# Bopit.net
KiCad netlist of a schematic drawn in Altium Designer
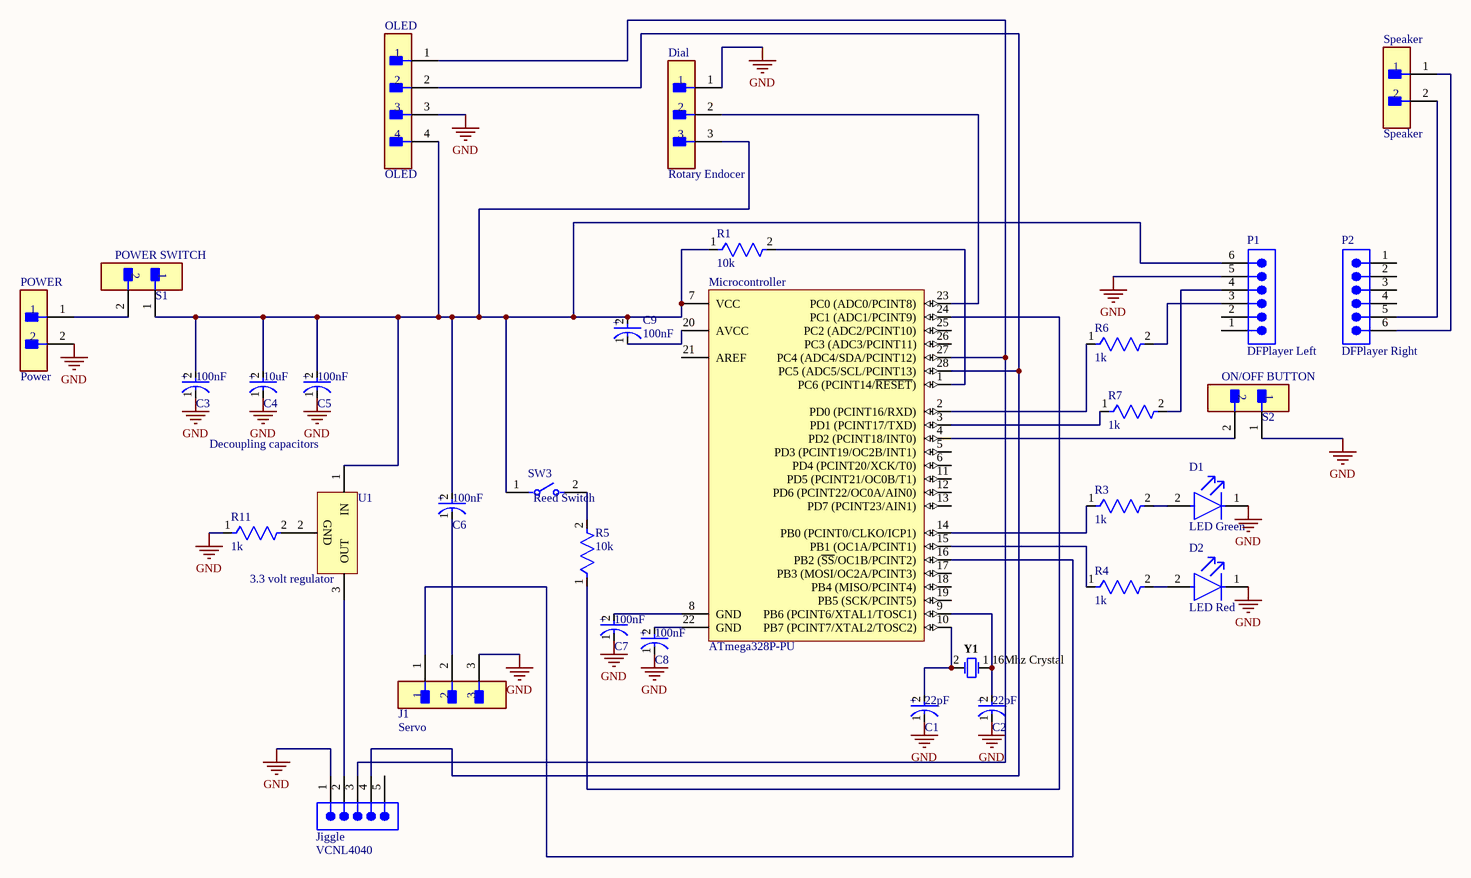
[diagram p0: Bopit.SchDoc]

(export (version "E")
  (design (tool "Eeschema 10.0.6"))
  (components
    (comp (ref "C1")
      (value "22pF")
      (footprint "FP-RAD-TH-D_6_3_0_5-L_11-MFG")
      (description "Aluminum Electrolytic Capacitors (Radial Lead Type) 2.2uF ±20% 250V")
      (fields (field (name "TOLERANCE") "20%"))
      (libsource (lib "Altium Content Vault") (part "203bc49f2ac43e59fd269a8c329ed05"))
    )
    (comp (ref "C2")
      (value "22pF")
      (footprint "FP-RAD-TH-D_6_3_0_5-L_11-MFG")
      (description "Aluminum Electrolytic Capacitors (Radial Lead Type) 2.2uF ±20% 250V")
      (fields (field (name "TOLERANCE") "20%"))
      (libsource (lib "Altium Content Vault") (part "203bc49f2ac43e59fd269a8c329ed05"))
    )
    (comp (ref "C3")
      (value "100nF")
      (footprint "FP-RAD-TH-D_6_3_0_5-L_11-MFG")
      (description "Aluminum Electrolytic Capacitors (Radial Lead Type) 2.2uF ±20% 250V")
      (fields (field (name "TOLERANCE") "20%"))
      (libsource (lib "Altium Content Vault") (part "203bc49f2ac43e59fd269a8c329ed05"))
    )
    (comp (ref "C4")
      (value "10uF")
      (footprint "FP-RAD-TH-D_6_3_0_5-L_11-MFG")
      (description "Aluminum Electrolytic Capacitors (Radial Lead Type) 2.2uF ±20% 250V")
      (fields (field (name "TOLERANCE") "20%"))
      (libsource (lib "Altium Content Vault") (part "203bc49f2ac43e59fd269a8c329ed05"))
    )
    (comp (ref "C5")
      (value "100nF")
      (footprint "FP-RAD-TH-D_6_3_0_5-L_11-MFG")
      (description "Aluminum Electrolytic Capacitors (Radial Lead Type) 2.2uF ±20% 250V")
      (fields (field (name "TOLERANCE") "20%"))
      (libsource (lib "Altium Content Vault") (part "203bc49f2ac43e59fd269a8c329ed05"))
    )
    (comp (ref "C6")
      (value "100nF")
      (footprint "FP-RAD-TH-D_6_3_0_5-L_11-MFG")
      (description "Aluminum Electrolytic Capacitors (Radial Lead Type) 2.2uF ±20% 250V")
      (fields (field (name "TOLERANCE") "20%"))
      (libsource (lib "Altium Content Vault") (part "203bc49f2ac43e59fd269a8c329ed05"))
    )
    (comp (ref "C7")
      (value "100nF")
      (footprint "FP-RAD-TH-D_6_3_0_5-L_11-MFG")
      (description "Aluminum Electrolytic Capacitors (Radial Lead Type) 2.2uF ±20% 250V")
      (fields (field (name "TOLERANCE") "20%"))
      (libsource (lib "Altium Content Vault") (part "203bc49f2ac43e59fd269a8c329ed05"))
    )
    (comp (ref "C8")
      (value "100nF")
      (footprint "FP-RAD-TH-D_6_3_0_5-L_11-MFG")
      (description "Aluminum Electrolytic Capacitors (Radial Lead Type) 2.2uF ±20% 250V")
      (fields (field (name "TOLERANCE") "20%"))
      (libsource (lib "Altium Content Vault") (part "203bc49f2ac43e59fd269a8c329ed05"))
    )
    (comp (ref "C9")
      (value "100nF")
      (footprint "FP-RAD-TH-D_6_3_0_5-L_11-MFG")
      (description "Aluminum Electrolytic Capacitors (Radial Lead Type) 2.2uF ±20% 250V")
      (fields (field (name "TOLERANCE") "20%"))
      (libsource (lib "Altium Content Vault") (part "203bc49f2ac43e59fd269a8c329ed05"))
    )
    (comp (ref "D1")
      (value "LED Green")
      (footprint "FP-SSL-LX5093YD-MFG")
      (description "LED YELLOW DIFFUSED T-1 3/4 T/H")
      (libsource (lib "Altium Content Vault") (part "8706943c75ba83719d021d2fdc84c58"))
    )
    (comp (ref "D2")
      (value "LED Red")
      (footprint "FP-SSL-LX5093YD-MFG")
      (description "LED YELLOW DIFFUSED T-1 3/4 T/H")
      (libsource (lib "Altium Content Vault") (part "8706943c75ba83719d021d2fdc84c58"))
    )
    (comp (ref "Dial")
      (value "Rotary Endocer")
      (footprint "FP-TSW-103-14-G-S-MFG")
      (description "CONN HEADER VERT 3POS 2.54MM")
      (libsource (lib "Altium Content Vault") (part "cd3439d6ef35ae5d9b27ec4fdd3e828"))
    )
    (comp (ref "J1")
      (value "Servo")
      (footprint "FP-TSW-103-14-G-S-MFG")
      (description "CONN HEADER VERT 3POS 2.54MM")
      (libsource (lib "") (part "cd3439d6ef35ae5d9b27ec4fdd3e828_1"))
    )
    (comp (ref "Jiggle")
      (value "VCNL4040")
      (footprint "SMTC-TSW-105-05-X-S")
      (description "0.025\" SQ Post Header, Through-hole, Vertical, -55 to 125 degC, 2.54 mm Pitch, 5-Pin, Male, RoHS")
      (fields (field (name "PARTNUMBER") "TSW-105-05-L-S") (field (name "MANUFACTURER") "Samtec"))
      (libsource (lib "Altium Content Vault") (part "SMTC-TSW-105-05-X-S"))
    )
    (comp (ref "Microcontroller")
      (value "ATmega328P-PU")
      (footprint "28P3")
      (libsource (lib "Altium Content Vault") (part "MC-8B-ATM48-IL28"))
    )
    (comp (ref "OLED")
      (value "OLED")
      (footprint "FP-TSW-104-22-G-S-MFG")
      (description "CONN HEADER VERT 4POS 2.54MM")
      (libsource (lib "Altium Content Vault") (part "299a8cea1bdcbc3624fe62c390fa72c"))
    )
    (comp (ref "P1")
      (value "DFPlayer Left")
      (footprint "SMTC-TSW-106-17-X-S-LL")
      (description "0.025\" SQ Post Header, Through-hole, Vertical, -55 to 125 degC, 2.54 mm Pitch, 6-Pin, Male, RoHS")
      (fields (field (name "PARTNUMBER") "TSW-106-17-L-S-LL") (field (name "MANUFACTURER") "Samtec"))
      (libsource (lib "Altium Content Vault") (part "SMTC-TSW-106-X-X-S-X"))
    )
    (comp (ref "P2")
      (value "DFPlayer Right")
      (footprint "SMTC-TSW-106-17-X-S-LL")
      (description "0.025\" SQ Post Header, Through-hole, Vertical, -55 to 125 degC, 2.54 mm Pitch, 6-Pin, Male, RoHS")
      (fields (field (name "PARTNUMBER") "TSW-106-17-L-S-LL") (field (name "MANUFACTURER") "Samtec"))
      (libsource (lib "Altium Content Vault") (part "SMTC-TSW-106-X-X-S-X"))
    )
    (comp (ref "POWER")
      (value "Power")
      (footprint "FP-TMM-102-03-F-S-MFG")
      (description "CONN HEADER VERT 2POS 2MM")
      (libsource (lib "Altium Content Vault") (part "3bc925449376181038e59eaffc5286c"))
    )
    (comp (ref "R1")
      (value "10k")
      (footprint "FP-FMP100-MFG")
      (description "Resistor, 1 kOhm, ± 5%, 1 W, Axial Leaded, Metal Film, High Power Flame Proof")
      (fields (field (name "TOLERANCE") "5%"))
      (libsource (lib "Altium Content Vault") (part "FMP100JT-52-1K"))
    )
    (comp (ref "R3")
      (value "1k")
      (footprint "FP-FMP100-MFG")
      (description "Resistor, 1 kOhm, ± 5%, 1 W, Axial Leaded, Metal Film, High Power Flame Proof")
      (fields (field (name "TOLERANCE") "5%"))
      (libsource (lib "Altium Content Vault") (part "FMP100JT-52-1K"))
    )
    (comp (ref "R4")
      (value "1k")
      (footprint "FP-FMP100-MFG")
      (description "Resistor, 1 kOhm, ± 5%, 1 W, Axial Leaded, Metal Film, High Power Flame Proof")
      (fields (field (name "TOLERANCE") "5%"))
      (libsource (lib "Altium Content Vault") (part "FMP100JT-52-1K"))
    )
    (comp (ref "R5")
      (value "10k")
      (footprint "FP-FMP100-MFG")
      (description "Resistor, 1 kOhm, ± 5%, 1 W, Axial Leaded, Metal Film, High Power Flame Proof")
      (fields (field (name "TOLERANCE") "5%"))
      (libsource (lib "Altium Content Vault") (part "FMP100JT-52-1K"))
    )
    (comp (ref "R6")
      (value "1k")
      (footprint "FP-FMP100-MFG")
      (description "Resistor, 1 kOhm, ± 5%, 1 W, Axial Leaded, Metal Film, High Power Flame Proof")
      (fields (field (name "TOLERANCE") "5%"))
      (libsource (lib "Altium Content Vault") (part "FMP100JT-52-1K"))
    )
    (comp (ref "R7")
      (value "1k")
      (footprint "FP-FMP100-MFG")
      (description "Resistor, 1 kOhm, ± 5%, 1 W, Axial Leaded, Metal Film, High Power Flame Proof")
      (fields (field (name "TOLERANCE") "5%"))
      (libsource (lib "Altium Content Vault") (part "FMP100JT-52-1K"))
    )
    (comp (ref "R11")
      (value "1k")
      (footprint "FP-FMP100-MFG")
      (description "Resistor, 1 kOhm, ± 5%, 1 W, Axial Leaded, Metal Film, High Power Flame Proof")
      (fields (field (name "TOLERANCE") "5%"))
      (libsource (lib "Altium Content Vault") (part "FMP100JT-52-1K"))
    )
    (comp (ref "S1")
      (value "POWER SWITCH")
      (footprint "FP-TMM-102-04-G-S-MFG")
      (description "2MM TERMINAL STRIP")
      (libsource (lib "") (part "3bc925449376181038e59eaffc5286c_1"))
    )
    (comp (ref "S2")
      (value "ON/OFF BUTTON")
      (footprint "FP-TMM-102-04-G-S-MFG")
      (description "2MM TERMINAL STRIP")
      (libsource (lib "") (part "3bc925449376181038e59eaffc5286c_1"))
    )
    (comp (ref "Speaker")
      (value "Speaker")
      (footprint "FP-TMM-102-03-F-S-MFG")
      (description "CONN HEADER VERT 2POS 2MM")
      (libsource (lib "Altium Content Vault") (part "3bc925449376181038e59eaffc5286c"))
    )
    (comp (ref "SW3")
      (value "Reed Switch")
      (footprint "FP-MLRR-3-17-23-MFG")
      (description "SWITCH REED SPST-NO 700MA 140V")
      (libsource (lib "Altium Content Vault") (part "bb27bde45df87f1f469753f287ef5ae"))
    )
    (comp (ref "U1")
      (value "3.3 volt regulator")
      (footprint "ONSC-TO-220-3-221AB-01")
      (description "Positive Voltage Regulator, 1 A, 5 V, 0 to 125 degC, 3-Pin TO-220, RoHS, Tube")
      (fields (field (name "MANUFACTURER") "ON Semiconductor"))
      (libsource (lib "Altium Content Vault") (part "ONSC-MC7805CTG-TO-220-3"))
    )
    (comp (ref "Y1")
      (value "16Mhz Crystal")
      (footprint "FOX-FOXSLF160-20")
      (description "Resistance Weld Thru-Hole Crystal, 16 MHz, -20 to 70 degC, 2-Pin THD, RoHS, Bulk")
      (fields (field (name "TOLERANCE") "1%"))
      (libsource (lib "Altium Content Vault") (part "XTAL-1-2-2"))
    )
  )
  (nets
    (net (code "1") (name "GND") (class "Default")
      (node (ref "C1") (pin "1") (pinfunction "C_1") (pintype "passive"))
      (node (ref "C2") (pin "1") (pinfunction "C_1") (pintype "passive"))
      (node (ref "C3") (pin "1") (pinfunction "C_1") (pintype "passive"))
      (node (ref "C4") (pin "1") (pinfunction "C_1") (pintype "passive"))
      (node (ref "C5") (pin "1") (pinfunction "C_1") (pintype "passive"))
      (node (ref "C7") (pin "1") (pinfunction "C_1") (pintype "passive"))
      (node (ref "C8") (pin "1") (pinfunction "C_1") (pintype "passive"))
      (node (ref "D1") (pin "1") (pinfunction "C_1") (pintype "passive"))
      (node (ref "D2") (pin "1") (pinfunction "C_1") (pintype "passive"))
      (node (ref "Dial") (pin "1") (pinfunction "1_1") (pintype "passive"))
      (node (ref "J1") (pin "3") (pinfunction "3_3") (pintype "passive"))
      (node (ref "Jiggle") (pin "1") (pinfunction "1_1") (pintype "passive"))
      (node (ref "OLED") (pin "3") (pinfunction "3_3") (pintype "passive"))
      (node (ref "P1") (pin "5") (pinfunction "5_5") (pintype "passive"))
      (node (ref "POWER") (pin "2") (pinfunction "2_2") (pintype "passive"))
      (node (ref "R11") (pin "1") (pinfunction "1_1") (pintype "passive"))
      (node (ref "S2") (pin "1") (pinfunction "1_1") (pintype "passive"))
    )
    (net (code "2") (name "Net-(C1-A)") (class "Default")
      (node (ref "C1") (pin "2") (pinfunction "A_2") (pintype "passive"))
      (node (ref "Microcontroller") (pin "10") (pinfunction "PB7_(PCINT7/XTAL2/TOSC2)_10") (pintype "bidirectional"))
      (node (ref "Y1") (pin "2") (pinfunction "2_2") (pintype "passive"))
    )
    (net (code "3") (name "Net-(C2-A)") (class "Default")
      (node (ref "C2") (pin "2") (pinfunction "A_2") (pintype "passive"))
      (node (ref "Microcontroller") (pin "9") (pinfunction "PB6_(PCINT6/XTAL1/TOSC1)_9") (pintype "bidirectional"))
      (node (ref "Y1") (pin "1") (pinfunction "1_1") (pintype "passive"))
    )
    (net (code "4") (name "Net-(C3-A)") (class "Default")
      (node (ref "C3") (pin "2") (pinfunction "A_2") (pintype "passive"))
      (node (ref "C4") (pin "2") (pinfunction "A_2") (pintype "passive"))
      (node (ref "C5") (pin "2") (pinfunction "A_2") (pintype "passive"))
      (node (ref "C6") (pin "2") (pinfunction "A_2") (pintype "passive"))
      (node (ref "C9") (pin "2") (pinfunction "A_2") (pintype "passive"))
      (node (ref "Dial") (pin "3") (pinfunction "3_3") (pintype "passive"))
      (node (ref "Microcontroller") (pin "7") (pinfunction "VCC_7") (pintype "power_in"))
      (node (ref "OLED") (pin "4") (pinfunction "4_4") (pintype "passive"))
      (node (ref "P1") (pin "6") (pinfunction "6_6") (pintype "passive"))
      (node (ref "R1") (pin "1") (pinfunction "1_1") (pintype "passive"))
      (node (ref "S1") (pin "1") (pinfunction "1_1") (pintype "passive"))
      (node (ref "SW3") (pin "1") (pinfunction "1_1") (pintype "passive"))
      (node (ref "U1") (pin "1") (pinfunction "IN_1") (pintype "power_in"))
    )
    (net (code "5") (name "Net-(C6-C)") (class "Default")
      (node (ref "C6") (pin "1") (pinfunction "C_1") (pintype "passive"))
      (node (ref "J1") (pin "2") (pinfunction "2_2") (pintype "passive"))
    )
    (net (code "6") (name "Net-(C7-A)") (class "Default")
      (node (ref "C7") (pin "2") (pinfunction "A_2") (pintype "passive"))
      (node (ref "Microcontroller") (pin "8") (pinfunction "GND_8") (pintype "power_in"))
    )
    (net (code "7") (name "Net-(C8-A)") (class "Default")
      (node (ref "C8") (pin "2") (pinfunction "A_2") (pintype "passive"))
      (node (ref "Microcontroller") (pin "22") (pinfunction "GND_22") (pintype "power_in"))
    )
    (net (code "8") (name "Net-(C9-C)") (class "Default")
      (node (ref "C9") (pin "1") (pinfunction "C_1") (pintype "passive"))
      (node (ref "Microcontroller") (pin "20") (pinfunction "AVCC_20") (pintype "power_in"))
    )
    (net (code "9") (name "Net-(D1-A)") (class "Default")
      (node (ref "D1") (pin "2") (pinfunction "A_2") (pintype "passive"))
      (node (ref "R3") (pin "2") (pinfunction "2_2") (pintype "passive"))
    )
    (net (code "10") (name "Net-(D2-A)") (class "Default")
      (node (ref "D2") (pin "2") (pinfunction "A_2") (pintype "passive"))
      (node (ref "R4") (pin "2") (pinfunction "2_2") (pintype "passive"))
    )
    (net (code "11") (name "Net-(Microcontroller-PB0_(PCINT0{slash}CLKO{slash}ICP1))") (class "Default")
      (node (ref "Microcontroller") (pin "14") (pinfunction "PB0_(PCINT0/CLKO/ICP1)_14") (pintype "bidirectional"))
      (node (ref "R3") (pin "1") (pinfunction "1_1") (pintype "passive"))
    )
    (net (code "12") (name "Net-(Microcontroller-PB1_(OC1A{slash}PCINT1))") (class "Default")
      (node (ref "Microcontroller") (pin "15") (pinfunction "PB1_(OC1A/PCINT1)_15") (pintype "bidirectional"))
      (node (ref "R4") (pin "1") (pinfunction "1_1") (pintype "passive"))
    )
    (net (code "13") (name "Net-(Microcontroller-PB2_(~{SS}{slash}OC1B{slash}PCINT2))") (class "Default")
      (node (ref "J1") (pin "1") (pinfunction "1_1") (pintype "passive"))
      (node (ref "Microcontroller") (pin "16") (pinfunction "PB2_(~{SS}/OC1B/PCINT2)_16") (pintype "bidirectional"))
    )
    (net (code "14") (name "Net-(Microcontroller-PC0_(ADC0{slash}PCINT8))") (class "Default")
      (node (ref "Dial") (pin "2") (pinfunction "2_2") (pintype "passive"))
      (node (ref "Microcontroller") (pin "23") (pinfunction "PC0_(ADC0/PCINT8)_23") (pintype "bidirectional"))
    )
    (net (code "15") (name "Net-(Microcontroller-PC1_(ADC1{slash}PCINT9))") (class "Default")
      (node (ref "Microcontroller") (pin "24") (pinfunction "PC1_(ADC1/PCINT9)_24") (pintype "bidirectional"))
      (node (ref "R5") (pin "1") (pinfunction "1_1") (pintype "passive"))
    )
    (net (code "16") (name "Net-(Microcontroller-PC4_(ADC4{slash}SDA{slash}PCINT12))") (class "Default")
      (node (ref "Jiggle") (pin "3") (pinfunction "3_3") (pintype "passive"))
      (node (ref "Microcontroller") (pin "27") (pinfunction "PC4_(ADC4/SDA/PCINT12)_27") (pintype "bidirectional"))
      (node (ref "OLED") (pin "1") (pinfunction "1_1") (pintype "passive"))
    )
    (net (code "17") (name "Net-(Microcontroller-PC5_(ADC5{slash}SCL{slash}PCINT13))") (class "Default")
      (node (ref "Jiggle") (pin "4") (pinfunction "4_4") (pintype "passive"))
      (node (ref "Microcontroller") (pin "28") (pinfunction "PC5_(ADC5/SCL/PCINT13)_28") (pintype "bidirectional"))
      (node (ref "OLED") (pin "2") (pinfunction "2_2") (pintype "passive"))
    )
    (net (code "18") (name "Net-(Microcontroller-PC6_(PCINT14{slash}~{RESET}))") (class "Default")
      (node (ref "Microcontroller") (pin "1") (pinfunction "PC6_(PCINT14/~{RESET})_1") (pintype "bidirectional"))
      (node (ref "R1") (pin "2") (pinfunction "2_2") (pintype "passive"))
    )
    (net (code "19") (name "Net-(Microcontroller-PD0_(PCINT16{slash}RXD))") (class "Default")
      (node (ref "Microcontroller") (pin "2") (pinfunction "PD0_(PCINT16/RXD)_2") (pintype "bidirectional"))
      (node (ref "R6") (pin "1") (pinfunction "1_1") (pintype "passive"))
    )
    (net (code "20") (name "Net-(Microcontroller-PD1_(PCINT17{slash}TXD))") (class "Default")
      (node (ref "Microcontroller") (pin "3") (pinfunction "PD1_(PCINT17/TXD)_3") (pintype "bidirectional"))
      (node (ref "R7") (pin "1") (pinfunction "1_1") (pintype "passive"))
    )
    (net (code "21") (name "Net-(Microcontroller-PD2_(PCINT18{slash}INT0))") (class "Default")
      (node (ref "Microcontroller") (pin "4") (pinfunction "PD2_(PCINT18/INT0)_4") (pintype "bidirectional"))
      (node (ref "S2") (pin "2") (pinfunction "2_2") (pintype "passive"))
    )
    (net (code "22") (name "Net-(P1-Pad3)") (class "Default")
      (node (ref "P1") (pin "3") (pinfunction "3_3") (pintype "passive"))
      (node (ref "R6") (pin "2") (pinfunction "2_2") (pintype "passive"))
    )
    (net (code "23") (name "Net-(P1-Pad4)") (class "Default")
      (node (ref "P1") (pin "4") (pinfunction "4_4") (pintype "passive"))
      (node (ref "R7") (pin "2") (pinfunction "2_2") (pintype "passive"))
    )
    (net (code "24") (name "Net-(P2-Pad5)") (class "Default")
      (node (ref "P2") (pin "5") (pinfunction "5_5") (pintype "passive"))
      (node (ref "Speaker") (pin "2") (pinfunction "2_2") (pintype "passive"))
    )
    (net (code "25") (name "Net-(P2-Pad6)") (class "Default")
      (node (ref "P2") (pin "6") (pinfunction "6_6") (pintype "passive"))
      (node (ref "Speaker") (pin "1") (pinfunction "1_1") (pintype "passive"))
    )
    (net (code "26") (name "Net-(POWER-Pad1)") (class "Default")
      (node (ref "POWER") (pin "1") (pinfunction "1_1") (pintype "passive"))
      (node (ref "S1") (pin "2") (pinfunction "2_2") (pintype "passive"))
    )
    (net (code "27") (name "Net-(R5-Pad2)") (class "Default")
      (node (ref "R5") (pin "2") (pinfunction "2_2") (pintype "passive"))
      (node (ref "SW3") (pin "2") (pinfunction "2_2") (pintype "passive"))
    )
    (net (code "28") (name "Net-(U1-GND)") (class "Default")
      (node (ref "R11") (pin "2") (pinfunction "2_2") (pintype "passive"))
      (node (ref "U1") (pin "2") (pinfunction "GND_2") (pintype "power_in"))
    )
    (net (code "29") (name "Net-(U1-OUT)") (class "Default")
      (node (ref "Jiggle") (pin "2") (pinfunction "2_2") (pintype "passive"))
      (node (ref "U1") (pin "3") (pinfunction "OUT_3") (pintype "power_in"))
    )
    (net (code "30") (name "unconnected-(Jiggle-Pad5)") (class "Default")
      (node (ref "Jiggle") (pin "5") (pinfunction "5_5") (pintype "passive"))
    )
    (net (code "31") (name "unconnected-(Microcontroller-AREF-Pad21)") (class "Default")
      (node (ref "Microcontroller") (pin "21") (pinfunction "AREF_21") (pintype "power_in"))
    )
    (net (code "32") (name "unconnected-(Microcontroller-PB3_(MOSI{slash}OC2A{slash}PCINT3)-Pad17)") (class "Default")
      (node (ref "Microcontroller") (pin "17") (pinfunction "PB3_(MOSI/OC2A/PCINT3)_17") (pintype "bidirectional"))
    )
    (net (code "33") (name "unconnected-(Microcontroller-PB4_(MISO{slash}PCINT4)-Pad18)") (class "Default")
      (node (ref "Microcontroller") (pin "18") (pinfunction "PB4_(MISO/PCINT4)_18") (pintype "bidirectional"))
    )
    (net (code "34") (name "unconnected-(Microcontroller-PB5_(SCK{slash}PCINT5)-Pad19)") (class "Default")
      (node (ref "Microcontroller") (pin "19") (pinfunction "PB5_(SCK/PCINT5)_19") (pintype "bidirectional"))
    )
    (net (code "35") (name "unconnected-(Microcontroller-PC2_(ADC2{slash}PCINT10)-Pad25)") (class "Default")
      (node (ref "Microcontroller") (pin "25") (pinfunction "PC2_(ADC2/PCINT10)_25") (pintype "bidirectional"))
    )
    (net (code "36") (name "unconnected-(Microcontroller-PC3_(ADC3{slash}PCINT11)-Pad26)") (class "Default")
      (node (ref "Microcontroller") (pin "26") (pinfunction "PC3_(ADC3/PCINT11)_26") (pintype "bidirectional"))
    )
    (net (code "37") (name "unconnected-(Microcontroller-PD3_(PCINT19{slash}OC2B{slash}INT1)-Pad5)") (class "Default")
      (node (ref "Microcontroller") (pin "5") (pinfunction "PD3_(PCINT19/OC2B/INT1)_5") (pintype "bidirectional"))
    )
    (net (code "38") (name "unconnected-(Microcontroller-PD4_(PCINT20{slash}XCK{slash}T0)-Pad6)") (class "Default")
      (node (ref "Microcontroller") (pin "6") (pinfunction "PD4_(PCINT20/XCK/T0)_6") (pintype "bidirectional"))
    )
    (net (code "39") (name "unconnected-(Microcontroller-PD5_(PCINT21{slash}OC0B{slash}T1)-Pad11)") (class "Default")
      (node (ref "Microcontroller") (pin "11") (pinfunction "PD5_(PCINT21/OC0B/T1)_11") (pintype "bidirectional"))
    )
    (net (code "40") (name "unconnected-(Microcontroller-PD6_(PCINT22{slash}OC0A{slash}AIN0)-Pad12)") (class "Default")
      (node (ref "Microcontroller") (pin "12") (pinfunction "PD6_(PCINT22/OC0A/AIN0)_12") (pintype "bidirectional"))
    )
    (net (code "41") (name "unconnected-(Microcontroller-PD7_(PCINT23{slash}AIN1)-Pad13)") (class "Default")
      (node (ref "Microcontroller") (pin "13") (pinfunction "PD7_(PCINT23/AIN1)_13") (pintype "bidirectional"))
    )
    (net (code "42") (name "unconnected-(P1-Pad1)") (class "Default")
      (node (ref "P1") (pin "1") (pinfunction "1_1") (pintype "passive"))
    )
    (net (code "43") (name "unconnected-(P1-Pad2)") (class "Default")
      (node (ref "P1") (pin "2") (pinfunction "2_2") (pintype "passive"))
    )
    (net (code "44") (name "unconnected-(P2-Pad1)") (class "Default")
      (node (ref "P2") (pin "1") (pinfunction "1_1") (pintype "passive"))
    )
    (net (code "45") (name "unconnected-(P2-Pad2)") (class "Default")
      (node (ref "P2") (pin "2") (pinfunction "2_2") (pintype "passive"))
    )
    (net (code "46") (name "unconnected-(P2-Pad3)") (class "Default")
      (node (ref "P2") (pin "3") (pinfunction "3_3") (pintype "passive"))
    )
    (net (code "47") (name "unconnected-(P2-Pad4)") (class "Default")
      (node (ref "P2") (pin "4") (pinfunction "4_4") (pintype "passive"))
    )
  )
)
